# ro.net
KiCad netlist of a schematic drawn in EAGLE
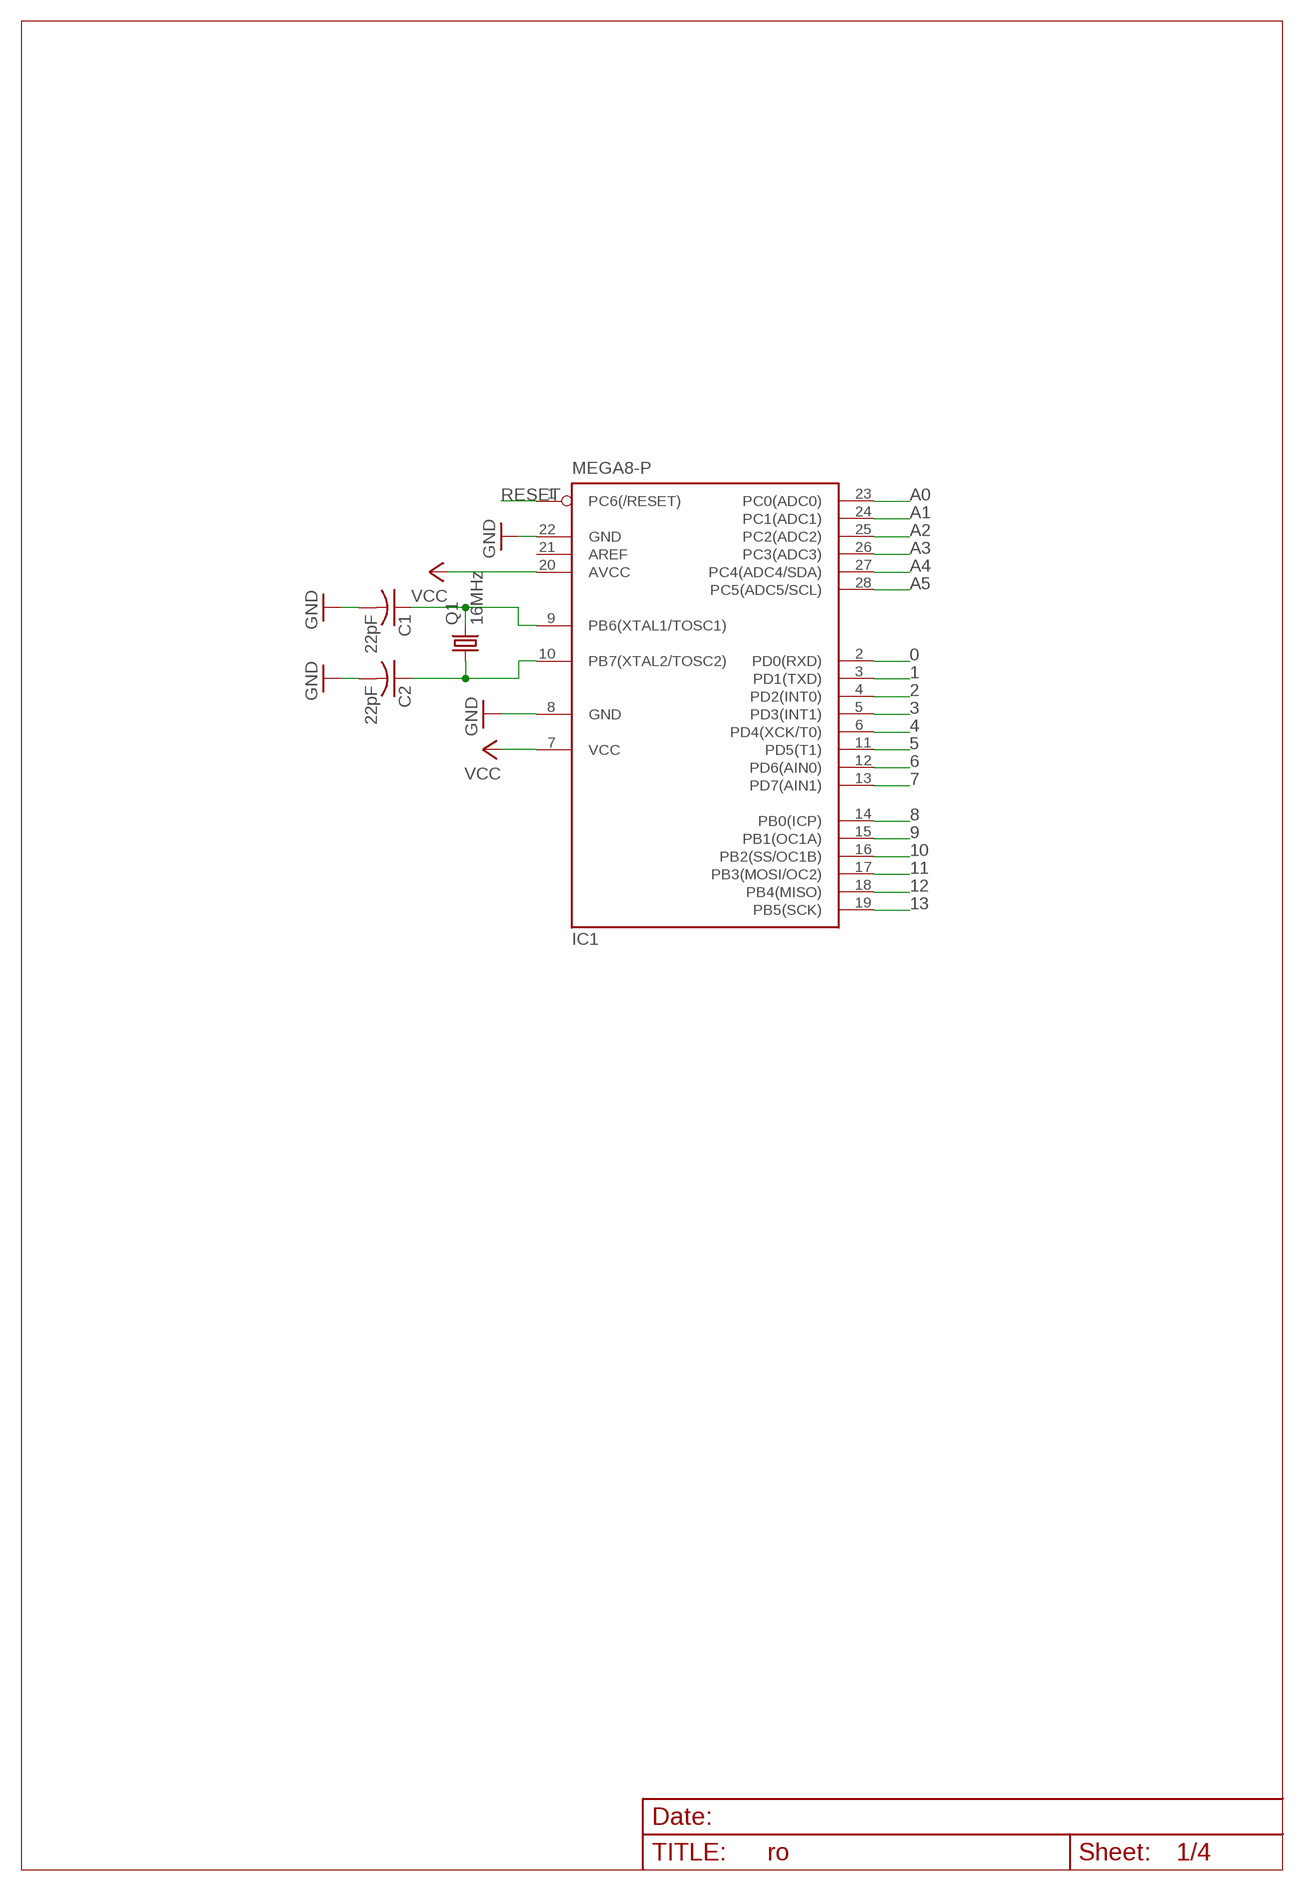
[diagram p0: schematic, sheet 1]
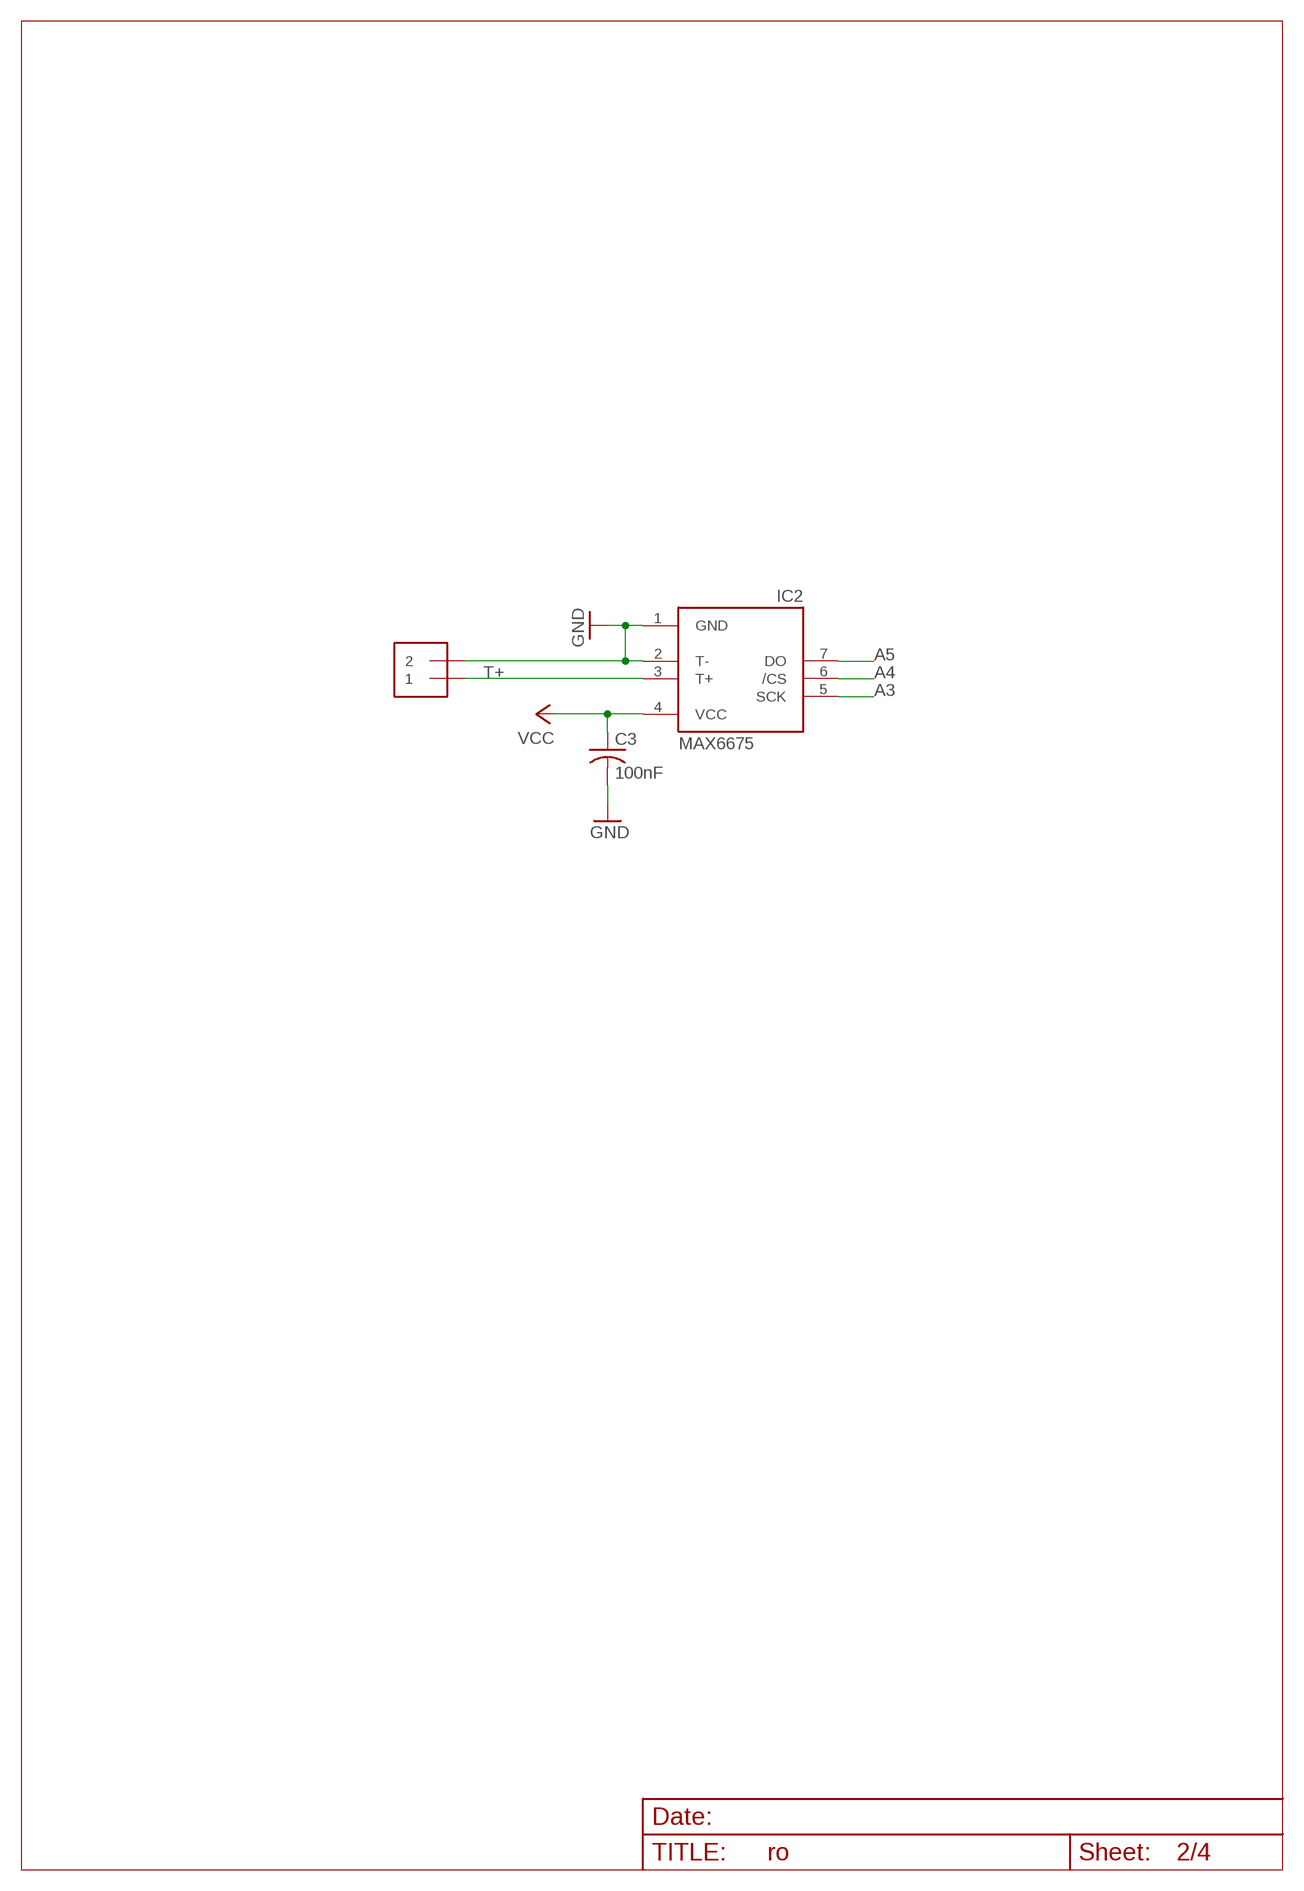
[diagram p1: schematic, sheet 2]
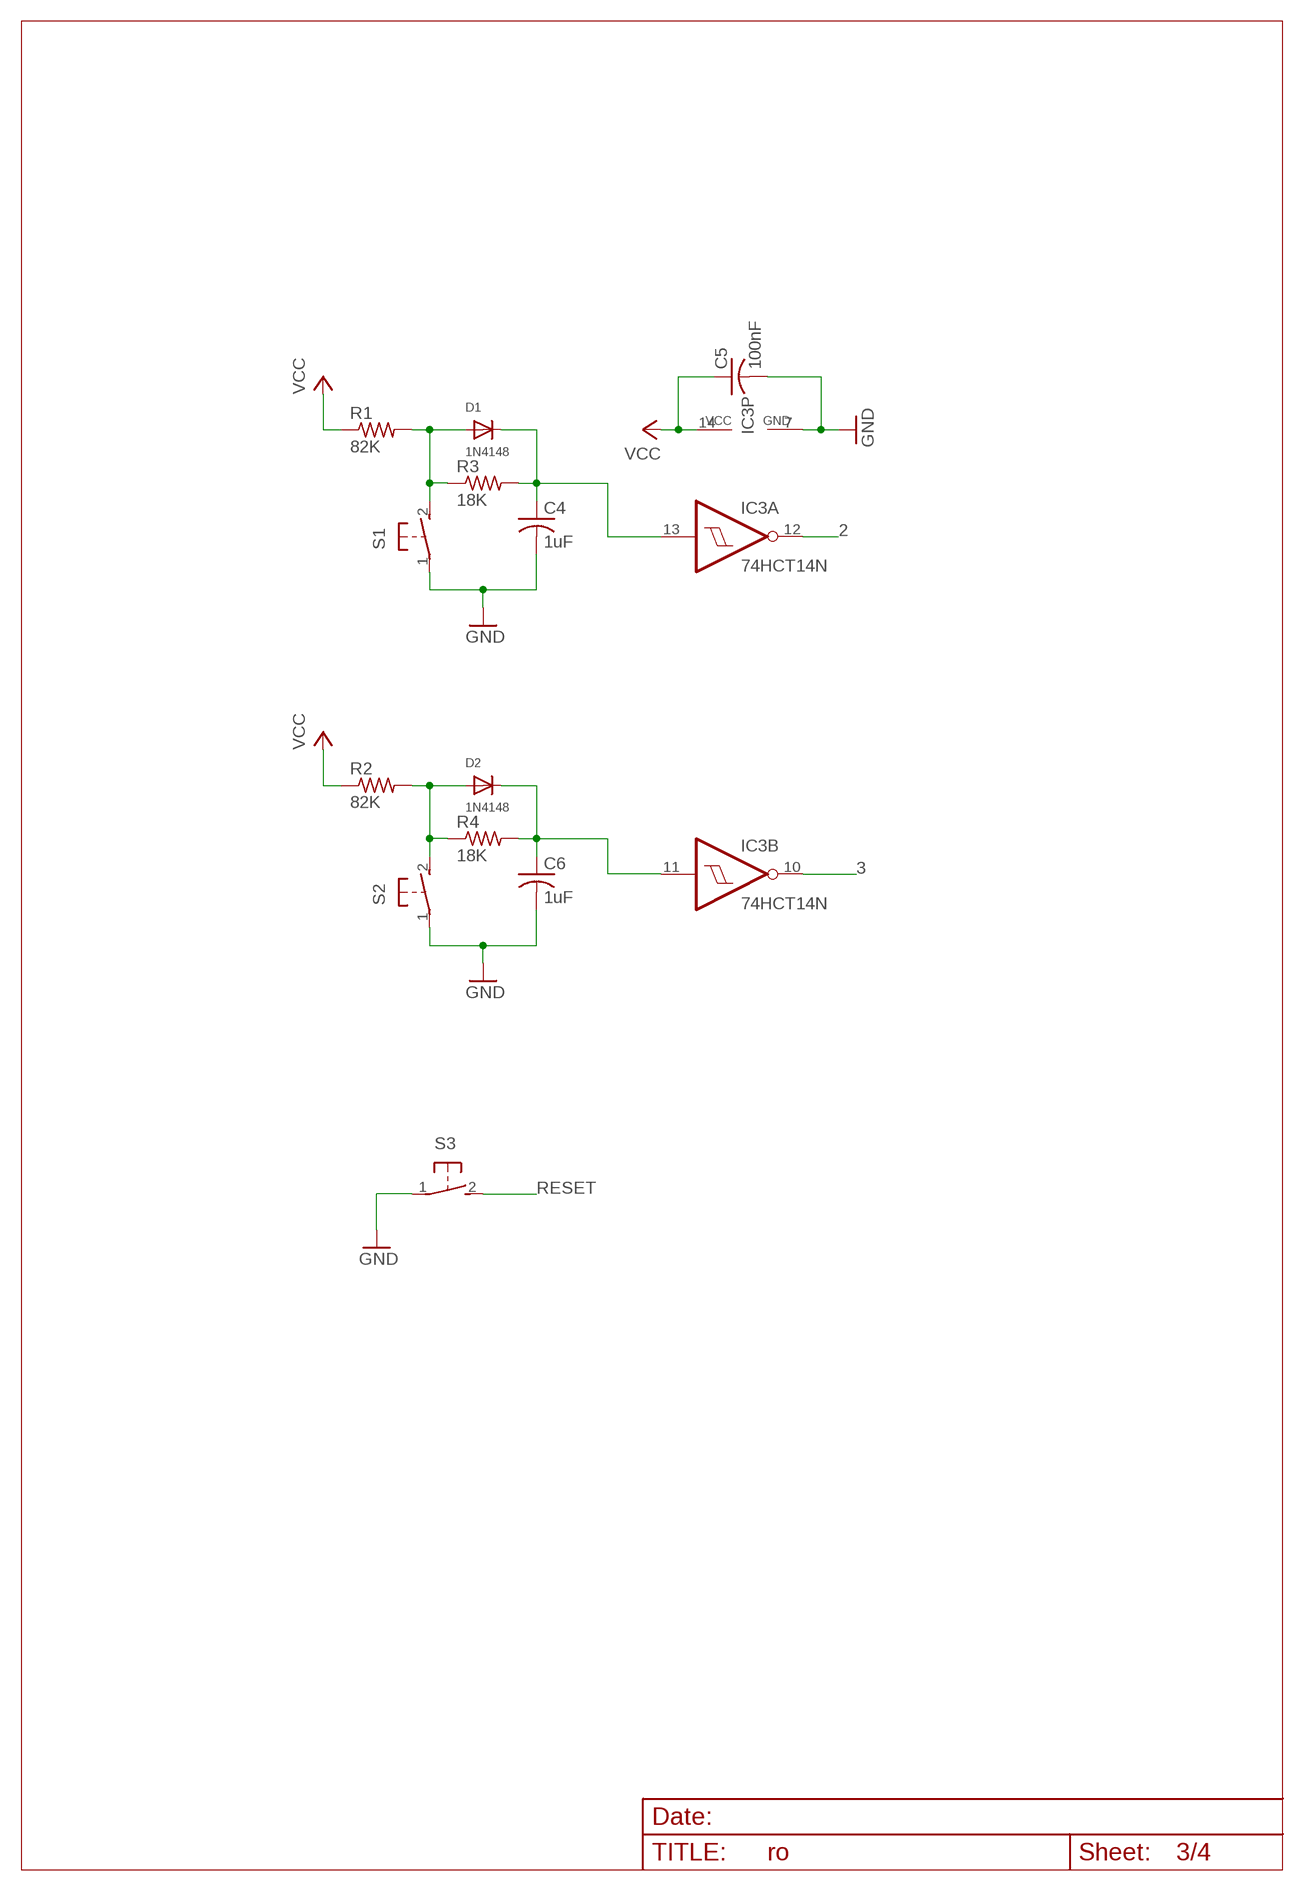
[diagram p2: schematic, sheet 3]
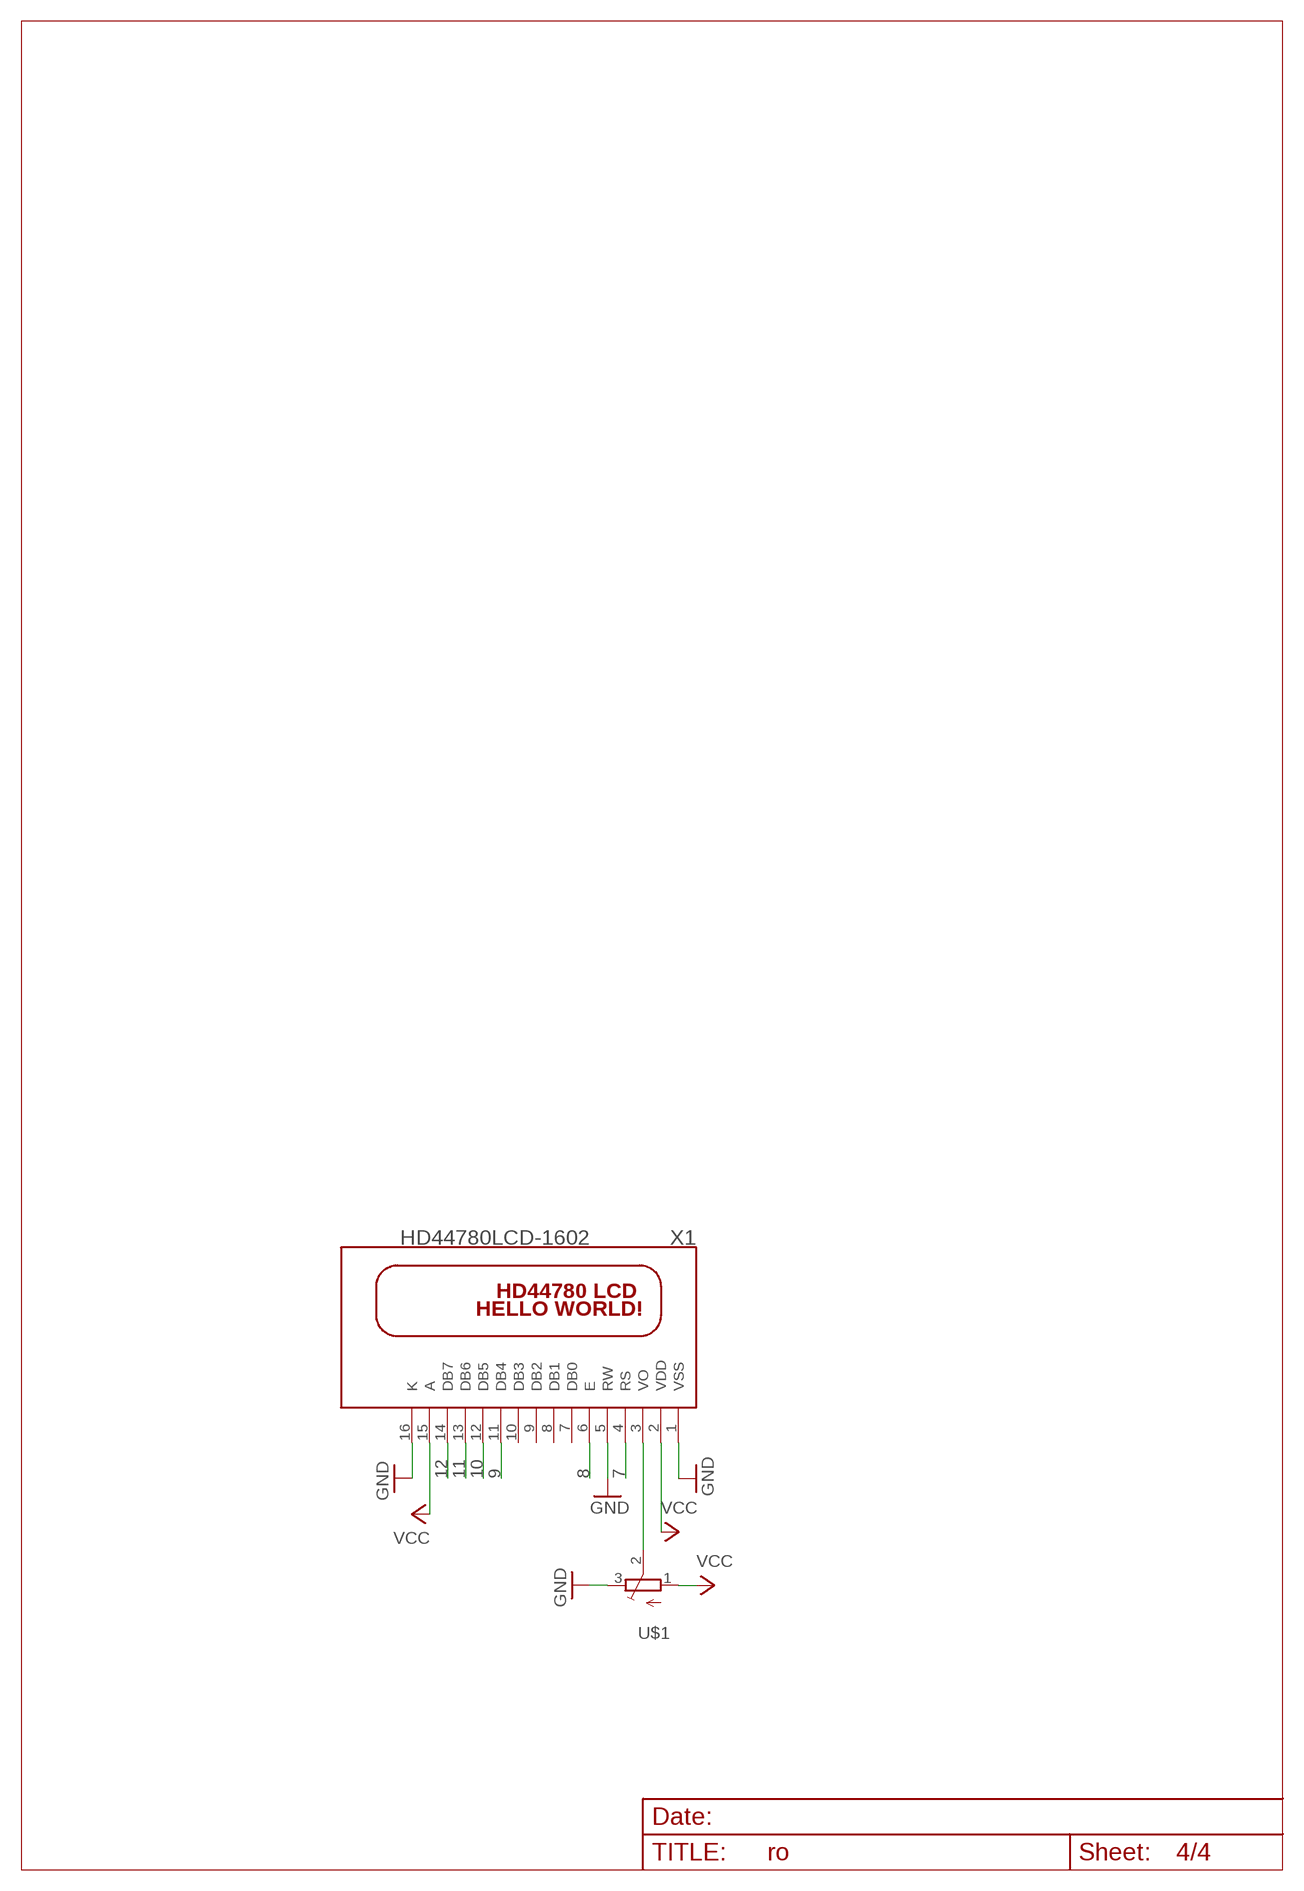
[diagram p3: schematic, sheet 4]

(export (version "E")
  (design (tool "Eeschema 10.0.6"))
  (components
    (comp (ref "C1")
      (value "22pF")
      (footprint "eagle-import:C025-025X050")
      (libsource (lib "eagle-import") (part "C-US025-025X050"))
    )
    (comp (ref "C2")
      (value "22pF")
      (footprint "eagle-import:C025-025X050")
      (libsource (lib "eagle-import") (part "C-US025-025X050"))
    )
    (comp (ref "IC1")
      (value "MEGA8-P")
      (footprint "eagle-import:DIL28-3")
      (libsource (lib "eagle-import") (part "MEGA8-P"))
    )
    (comp (ref "Q1")
      (value "16MHz")
      (footprint "eagle-import:HC49_S")
      (libsource (lib "eagle-import") (part "CRYSTALHC49S"))
    )
    (comp (ref "U$1")
      (value "TRIMPOTTC33X")
      (footprint "eagle-import:TC33X")
      (libsource (lib "eagle-import") (part "TRIMPOTTC33X"))
    )
    (comp (ref "X1")
      (value "HD44780LCD-1602")
      (footprint "eagle-import:LCD1602")
      (libsource (lib "eagle-import") (part "HD44780LCD-1602"))
    )
    (comp (ref "C4")
      (value "1uF")
      (footprint "eagle-import:C0805")
      (libsource (lib "eagle-import") (part "C-USC0805"))
    )
    (comp (ref "C5")
      (value "100nF")
      (footprint "eagle-import:C0805")
      (libsource (lib "eagle-import") (part "C-USC0805"))
    )
    (comp (ref "C6")
      (value "1uF")
      (footprint "eagle-import:C0805")
      (libsource (lib "eagle-import") (part "C-USC0805"))
    )
    (comp (ref "D1")
      (value "1N4148")
      (footprint "eagle-import:SMADIODE")
      (libsource (lib "eagle-import") (part "DIODESMA"))
    )
    (comp (ref "D2")
      (value "1N4148")
      (footprint "eagle-import:SMADIODE")
      (libsource (lib "eagle-import") (part "DIODESMA"))
    )
    (comp (ref "IC3")
      (value "74HCT14N")
      (footprint "eagle-import:DIL14")
      (libsource (lib "eagle-import") (part "7414NHCT"))
    )
    (comp (ref "R1")
      (value "82K")
      (footprint "eagle-import:R0805")
      (libsource (lib "eagle-import") (part "R-US_R0805"))
    )
    (comp (ref "R2")
      (value "82K")
      (footprint "eagle-import:R0805")
      (libsource (lib "eagle-import") (part "R-US_R0805"))
    )
    (comp (ref "R3")
      (value "18K")
      (footprint "eagle-import:R0805")
      (libsource (lib "eagle-import") (part "R-US_R0805"))
    )
    (comp (ref "R4")
      (value "18K")
      (footprint "eagle-import:R0805")
      (libsource (lib "eagle-import") (part "R-US_R0805"))
    )
    (comp (ref "S1")
      (value "31-XX")
      (footprint "eagle-import:B3F-31XX")
      (libsource (lib "eagle-import") (part "31-XX"))
    )
    (comp (ref "S2")
      (value "31-XX")
      (footprint "eagle-import:B3F-31XX")
      (libsource (lib "eagle-import") (part "31-XX"))
    )
    (comp (ref "S3")
      (value "31-XX")
      (footprint "eagle-import:B3F-31XX")
      (libsource (lib "eagle-import") (part "31-XX"))
    )
    (comp (ref "C3")
      (value "100nF")
      (footprint "eagle-import:C025-025X050")
      (libsource (lib "eagle-import") (part "C-US025-025X050"))
    )
    (comp (ref "IC2")
      (value "MAX6675")
      (footprint "eagle-import:SO08")
      (libsource (lib "eagle-import") (part "MAX6675"))
    )
    (comp (ref "TC")
      (value "1X2-3.5MM")
      (footprint "eagle-import:1X2-3.5MM")
      (libsource (lib "eagle-import") (part "1X2-3.5MM"))
    )
  )
  (nets
    (net (code "1") (name "0") (class "Default")
      (node (ref "IC1") (pin "2") (pinfunction "PD0(RXD)_2") (pintype "bidirectional"))
    )
    (net (code "2") (name "1") (class "Default")
      (node (ref "IC1") (pin "3") (pinfunction "PD1(TXD)_3") (pintype "bidirectional"))
    )
    (net (code "3") (name "2") (class "Default")
      (node (ref "IC1") (pin "4") (pinfunction "PD2(INT0)_4") (pintype "bidirectional"))
      (node (ref "IC3") (pin "12") (pinfunction "O_12") (pintype "output"))
    )
    (net (code "4") (name "3") (class "Default")
      (node (ref "IC1") (pin "5") (pinfunction "PD3(INT1)_5") (pintype "bidirectional"))
      (node (ref "IC3") (pin "10") (pinfunction "O_10") (pintype "output"))
    )
    (net (code "5") (name "4") (class "Default")
      (node (ref "IC1") (pin "6") (pinfunction "PD4(XCK/T0)_6") (pintype "bidirectional"))
    )
    (net (code "6") (name "5") (class "Default")
      (node (ref "IC1") (pin "11") (pinfunction "PD5(T1)_11") (pintype "bidirectional"))
    )
    (net (code "7") (name "6") (class "Default")
      (node (ref "IC1") (pin "12") (pinfunction "PD6(AIN0)_12") (pintype "bidirectional"))
    )
    (net (code "8") (name "7") (class "Default")
      (node (ref "IC1") (pin "13") (pinfunction "PD7(AIN1)_13") (pintype "bidirectional"))
      (node (ref "X1") (pin "4") (pinfunction "RS_4") (pintype "input"))
    )
    (net (code "9") (name "8") (class "Default")
      (node (ref "IC1") (pin "14") (pinfunction "PB0(ICP)_14") (pintype "bidirectional"))
      (node (ref "X1") (pin "6") (pinfunction "E_6") (pintype "input"))
    )
    (net (code "10") (name "9") (class "Default")
      (node (ref "IC1") (pin "15") (pinfunction "PB1(OC1A)_15") (pintype "bidirectional"))
      (node (ref "X1") (pin "11") (pinfunction "DB4_11") (pintype "bidirectional"))
    )
    (net (code "11") (name "10") (class "Default")
      (node (ref "IC1") (pin "16") (pinfunction "PB2(SS/OC1B)_16") (pintype "bidirectional"))
      (node (ref "X1") (pin "12") (pinfunction "DB5_12") (pintype "bidirectional"))
    )
    (net (code "12") (name "11") (class "Default")
      (node (ref "IC1") (pin "17") (pinfunction "PB3(MOSI/OC2)_17") (pintype "bidirectional"))
      (node (ref "X1") (pin "13") (pinfunction "DB6_13") (pintype "bidirectional"))
    )
    (net (code "13") (name "12") (class "Default")
      (node (ref "IC1") (pin "18") (pinfunction "PB4(MISO)_18") (pintype "bidirectional"))
      (node (ref "X1") (pin "14") (pinfunction "DB7_14") (pintype "bidirectional"))
    )
    (net (code "14") (name "13") (class "Default")
      (node (ref "IC1") (pin "19") (pinfunction "PB5(SCK)_19") (pintype "bidirectional"))
    )
    (net (code "15") (name "A0") (class "Default")
      (node (ref "IC1") (pin "23") (pinfunction "PC0(ADC0)_23") (pintype "bidirectional"))
    )
    (net (code "16") (name "A1") (class "Default")
      (node (ref "IC1") (pin "24") (pinfunction "PC1(ADC1)_24") (pintype "bidirectional"))
    )
    (net (code "17") (name "A2") (class "Default")
      (node (ref "IC1") (pin "25") (pinfunction "PC2(ADC2)_25") (pintype "bidirectional"))
    )
    (net (code "18") (name "A3") (class "Default")
      (node (ref "IC1") (pin "26") (pinfunction "PC3(ADC3)_26") (pintype "bidirectional"))
      (node (ref "IC2") (pin "5") (pinfunction "SCK_5") (pintype "input"))
    )
    (net (code "19") (name "A4") (class "Default")
      (node (ref "IC1") (pin "27") (pinfunction "PC4(ADC4/SDA)_27") (pintype "bidirectional"))
      (node (ref "IC2") (pin "6") (pinfunction "/CS_6") (pintype "input"))
    )
    (net (code "20") (name "A5") (class "Default")
      (node (ref "IC1") (pin "28") (pinfunction "PC5(ADC5/SCL)_28") (pintype "bidirectional"))
      (node (ref "IC2") (pin "7") (pinfunction "DO_7") (pintype "output"))
    )
    (net (code "21") (name "GND") (class "Default")
      (node (ref "C1") (pin "2") (pinfunction "2_2") (pintype "passive"))
      (node (ref "C2") (pin "2") (pinfunction "2_2") (pintype "passive"))
      (node (ref "C3") (pin "2") (pinfunction "2_2") (pintype "passive"))
      (node (ref "C4") (pin "2") (pinfunction "2_2") (pintype "passive"))
      (node (ref "C5") (pin "2") (pinfunction "2_2") (pintype "passive"))
      (node (ref "C6") (pin "2") (pinfunction "2_2") (pintype "passive"))
      (node (ref "IC1") (pin "22") (pinfunction "GND_22") (pintype "power_in"))
      (node (ref "IC1") (pin "8") (pinfunction "GND_8") (pintype "power_in"))
      (node (ref "IC2") (pin "1") (pinfunction "GND_1") (pintype "power_in"))
      (node (ref "IC2") (pin "2") (pinfunction "T-_2") (pintype "input"))
      (node (ref "IC3") (pin "7") (pinfunction "GND_7") (pintype "power_in"))
      (node (ref "S1") (pin "1") (pinfunction "P_1") (pintype "passive"))
      (node (ref "S2") (pin "1") (pinfunction "P_1") (pintype "passive"))
      (node (ref "S3") (pin "1") (pinfunction "P_1") (pintype "passive"))
      (node (ref "TC") (pin "2") (pinfunction "2_2") (pintype "passive"))
      (node (ref "U$1") (pin "3") (pinfunction "E_3") (pintype "passive"))
      (node (ref "X1") (pin "1") (pinfunction "VSS_1") (pintype "power_in"))
      (node (ref "X1") (pin "16") (pinfunction "K_16") (pintype "input"))
      (node (ref "X1") (pin "5") (pinfunction "RW_5") (pintype "input"))
    )
    (net (code "22") (name "Net-(IC1-PB6(XTAL1{slash}TOSC1))") (class "Default")
      (node (ref "C1") (pin "1") (pinfunction "1_1") (pintype "passive"))
      (node (ref "IC1") (pin "9") (pinfunction "PB6(XTAL1/TOSC1)_9") (pintype "bidirectional"))
      (node (ref "Q1") (pin "2") (pinfunction "2_2") (pintype "passive"))
    )
    (net (code "23") (name "Net-(IC1-PB7(XTAL2{slash}TOSC2))") (class "Default")
      (node (ref "C2") (pin "1") (pinfunction "1_1") (pintype "passive"))
      (node (ref "IC1") (pin "10") (pinfunction "PB7(XTAL2/TOSC2)_10") (pintype "bidirectional"))
      (node (ref "Q1") (pin "1") (pinfunction "1_1") (pintype "passive"))
    )
    (net (code "24") (name "Net-(IC3A-I)") (class "Default")
      (node (ref "C4") (pin "1") (pinfunction "1_1") (pintype "passive"))
      (node (ref "D1") (pin "C") (pinfunction "C_C") (pintype "passive"))
      (node (ref "IC3") (pin "13") (pinfunction "I_13") (pintype "input"))
      (node (ref "R3") (pin "2") (pinfunction "2_2") (pintype "passive"))
    )
    (net (code "25") (name "Net-(IC3B-I)") (class "Default")
      (node (ref "C6") (pin "1") (pinfunction "1_1") (pintype "passive"))
      (node (ref "D2") (pin "C") (pinfunction "C_C") (pintype "passive"))
      (node (ref "IC3") (pin "11") (pinfunction "I_11") (pintype "input"))
      (node (ref "R4") (pin "2") (pinfunction "2_2") (pintype "passive"))
    )
    (net (code "26") (name "Net-(S1-S)") (class "Default")
      (node (ref "D1") (pin "A") (pinfunction "A_A") (pintype "passive"))
      (node (ref "R1") (pin "2") (pinfunction "2_2") (pintype "passive"))
      (node (ref "R3") (pin "1") (pinfunction "1_1") (pintype "passive"))
      (node (ref "S1") (pin "2") (pinfunction "S_2") (pintype "passive"))
    )
    (net (code "27") (name "Net-(S2-S)") (class "Default")
      (node (ref "D2") (pin "A") (pinfunction "A_A") (pintype "passive"))
      (node (ref "R2") (pin "2") (pinfunction "2_2") (pintype "passive"))
      (node (ref "R4") (pin "1") (pinfunction "1_1") (pintype "passive"))
      (node (ref "S2") (pin "2") (pinfunction "S_2") (pintype "passive"))
    )
    (net (code "28") (name "Net-(U$1-S)") (class "Default")
      (node (ref "U$1") (pin "2") (pinfunction "S_2") (pintype "passive"))
      (node (ref "X1") (pin "3") (pinfunction "VO_3") (pintype "input"))
    )
    (net (code "29") (name "RESET") (class "Default")
      (node (ref "IC1") (pin "1") (pinfunction "PC6(/RESET)_1") (pintype "bidirectional"))
      (node (ref "S3") (pin "2") (pinfunction "S_2") (pintype "passive"))
    )
    (net (code "30") (name "T+") (class "Default")
      (node (ref "IC2") (pin "3") (pinfunction "T+_3") (pintype "input"))
      (node (ref "TC") (pin "1") (pinfunction "1_1") (pintype "passive"))
    )
    (net (code "31") (name "VCC") (class "Default")
      (node (ref "C3") (pin "1") (pinfunction "1_1") (pintype "passive"))
      (node (ref "C5") (pin "1") (pinfunction "1_1") (pintype "passive"))
      (node (ref "IC1") (pin "20") (pinfunction "AVCC_20") (pintype "power_in"))
      (node (ref "IC1") (pin "7") (pinfunction "VCC_7") (pintype "power_in"))
      (node (ref "IC2") (pin "4") (pinfunction "VCC_4") (pintype "power_in"))
      (node (ref "IC3") (pin "14") (pinfunction "VCC_14") (pintype "power_in"))
      (node (ref "R1") (pin "1") (pinfunction "1_1") (pintype "passive"))
      (node (ref "R2") (pin "1") (pinfunction "1_1") (pintype "passive"))
      (node (ref "U$1") (pin "1") (pinfunction "A_1") (pintype "passive"))
      (node (ref "X1") (pin "15") (pinfunction "A_15") (pintype "input"))
      (node (ref "X1") (pin "2") (pinfunction "VDD_2") (pintype "power_in"))
    )
    (net (code "32") (name "unconnected-(IC1-AREF-Pad21)") (class "Default")
      (node (ref "IC1") (pin "21") (pinfunction "AREF_21") (pintype "passive"))
    )
    (net (code "33") (name "unconnected-(X1-DB0-Pad7)") (class "Default")
      (node (ref "X1") (pin "7") (pinfunction "DB0_7") (pintype "bidirectional"))
    )
    (net (code "34") (name "unconnected-(X1-DB1-Pad8)") (class "Default")
      (node (ref "X1") (pin "8") (pinfunction "DB1_8") (pintype "bidirectional"))
    )
    (net (code "35") (name "unconnected-(X1-DB2-Pad9)") (class "Default")
      (node (ref "X1") (pin "9") (pinfunction "DB2_9") (pintype "bidirectional"))
    )
    (net (code "36") (name "unconnected-(X1-DB3-Pad10)") (class "Default")
      (node (ref "X1") (pin "10") (pinfunction "DB3_10") (pintype "bidirectional"))
    )
  )
)
